# interstage_B1v2.net
KiCad netlist of a schematic drawn in EAGLE
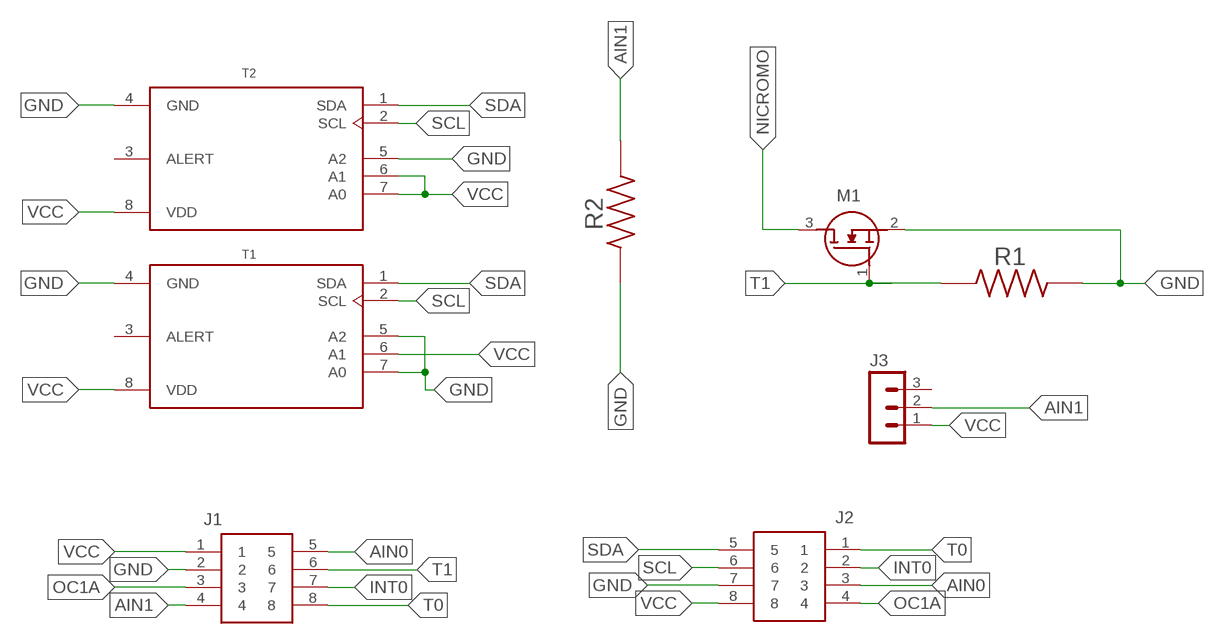
[diagram p0: schematic, sheet 1]

(export (version "E")
  (design (tool "Eeschema 10.0.6"))
  (components
    (comp (ref "J1")
      (value "53261-0871")
      (footprint "eagle-import:53261-0871")
      (fields (field (name "MOUSER_PART_NUMBER") "538-53261-0871"))
      (libsource (lib "eagle-import") (part "53261-0871"))
    )
    (comp (ref "J2")
      (value "53261-0871")
      (footprint "eagle-import:53261-0871")
      (fields (field (name "MOUSER_PART_NUMBER") "538-53261-0871"))
      (libsource (lib "eagle-import") (part "53261-0871"))
    )
    (comp (ref "J3")
      (value "MA03-1")
      (footprint "eagle-import:MA03-1")
      (libsource (lib "eagle-import") (part "MA03-1"))
    )
    (comp (ref "M1")
      (value "PMV16XNR")
      (footprint "eagle-import:SOT95P230X110-3N")
      (fields (field (name "MOUSER_PART_NUMBER") "771-PMV16XNR"))
      (libsource (lib "eagle-import") (part "PMV16XNR"))
    )
    (comp (ref "R1")
      (value "330")
      (footprint "eagle-import:RESC3216X70N")
      (fields
        (field (name "DIGI-KEY_PART_NUMBER") "P330BCCT-ND")
        (field (name "MF") "Panasonic Electronic")
        (field (name "MP") "ERA-8AEB331V")
      )
      (libsource (lib "eagle-import") (part "ERA-8AEB331V"))
    )
    (comp (ref "R2")
      (value "330")
      (footprint "eagle-import:RESC3216X70N")
      (fields
        (field (name "DIGI-KEY_PART_NUMBER") "P330BCCT-ND")
        (field (name "MF") "Panasonic Electronic")
        (field (name "MP") "ERA-8AEB331V")
      )
      (libsource (lib "eagle-import") (part "ERA-8AEB331V"))
    )
    (comp (ref "T1")
      (value "MCP9808T-E/MS")
      (footprint "eagle-import:SOP65P490X110-8N")
      (fields (field (name "DIGI-KEY_PART_NUMBER") "MCP9808T-E/MSCT-ND") (field (name "MF") "Microchip"))
      (libsource (lib "eagle-import") (part "MCP9808T-E/MS"))
    )
    (comp (ref "T2")
      (value "MCP9808T-E/MS")
      (footprint "eagle-import:SOP65P490X110-8N")
      (fields (field (name "DIGI-KEY_PART_NUMBER") "MCP9808T-E/MSCT-ND") (field (name "MF") "Microchip"))
      (libsource (lib "eagle-import") (part "MCP9808T-E/MS"))
    )
  )
  (nets
    (net (code "1") (name "AIN0") (class "Default")
      (node (ref "J1") (pin "5") (pinfunction "5_5") (pintype "bidirectional"))
      (node (ref "J2") (pin "3") (pinfunction "3_3") (pintype "bidirectional"))
    )
    (net (code "2") (name "AIN1") (class "Default")
      (node (ref "J1") (pin "4") (pinfunction "4_4") (pintype "bidirectional"))
      (node (ref "J3") (pin "2") (pinfunction "2_2") (pintype "passive"))
      (node (ref "R2") (pin "2") (pinfunction "2_2") (pintype "passive"))
    )
    (net (code "3") (name "GND") (class "Default")
      (node (ref "J1") (pin "2") (pinfunction "2_2") (pintype "bidirectional"))
      (node (ref "J2") (pin "7") (pinfunction "7_7") (pintype "bidirectional"))
      (node (ref "M1") (pin "2") (pinfunction "S_2") (pintype "bidirectional"))
      (node (ref "R1") (pin "2") (pinfunction "2_2") (pintype "passive"))
      (node (ref "R2") (pin "1") (pinfunction "1_1") (pintype "passive"))
      (node (ref "T1") (pin "4") (pinfunction "GND_4") (pintype "power_in"))
      (node (ref "T1") (pin "5") (pinfunction "A2_5") (pintype "input"))
      (node (ref "T1") (pin "7") (pinfunction "A0_7") (pintype "input"))
      (node (ref "T2") (pin "4") (pinfunction "GND_4") (pintype "power_in"))
      (node (ref "T2") (pin "5") (pinfunction "A2_5") (pintype "input"))
    )
    (net (code "4") (name "INT0") (class "Default")
      (node (ref "J1") (pin "7") (pinfunction "7_7") (pintype "bidirectional"))
      (node (ref "J2") (pin "2") (pinfunction "2_2") (pintype "bidirectional"))
    )
    (net (code "5") (name "NICROMO") (class "Default")
      (node (ref "M1") (pin "3") (pinfunction "D_3") (pintype "bidirectional"))
    )
    (net (code "6") (name "OC1A") (class "Default")
      (node (ref "J1") (pin "3") (pinfunction "3_3") (pintype "bidirectional"))
      (node (ref "J2") (pin "4") (pinfunction "4_4") (pintype "bidirectional"))
    )
    (net (code "7") (name "SCL") (class "Default")
      (node (ref "J2") (pin "6") (pinfunction "6_6") (pintype "bidirectional"))
      (node (ref "T1") (pin "2") (pinfunction "SCL_2") (pintype "input"))
      (node (ref "T2") (pin "2") (pinfunction "SCL_2") (pintype "input"))
    )
    (net (code "8") (name "SDA") (class "Default")
      (node (ref "J2") (pin "5") (pinfunction "5_5") (pintype "bidirectional"))
      (node (ref "T1") (pin "1") (pinfunction "SDA_1") (pintype "bidirectional"))
      (node (ref "T2") (pin "1") (pinfunction "SDA_1") (pintype "bidirectional"))
    )
    (net (code "9") (name "T0") (class "Default")
      (node (ref "J1") (pin "8") (pinfunction "8_8") (pintype "bidirectional"))
      (node (ref "J2") (pin "1") (pinfunction "1_1") (pintype "bidirectional"))
    )
    (net (code "10") (name "T1") (class "Default")
      (node (ref "J1") (pin "6") (pinfunction "6_6") (pintype "bidirectional"))
      (node (ref "M1") (pin "1") (pinfunction "G_1") (pintype "bidirectional"))
      (node (ref "R1") (pin "1") (pinfunction "1_1") (pintype "passive"))
    )
    (net (code "11") (name "VCC") (class "Default")
      (node (ref "J1") (pin "1") (pinfunction "1_1") (pintype "bidirectional"))
      (node (ref "J2") (pin "8") (pinfunction "8_8") (pintype "bidirectional"))
      (node (ref "J3") (pin "1") (pinfunction "1_1") (pintype "passive"))
      (node (ref "T1") (pin "6") (pinfunction "A1_6") (pintype "input"))
      (node (ref "T1") (pin "8") (pinfunction "VDD_8") (pintype "power_in"))
      (node (ref "T2") (pin "6") (pinfunction "A1_6") (pintype "input"))
      (node (ref "T2") (pin "7") (pinfunction "A0_7") (pintype "input"))
      (node (ref "T2") (pin "8") (pinfunction "VDD_8") (pintype "power_in"))
    )
    (net (code "12") (name "unconnected-(J3-Pad3)") (class "Default")
      (node (ref "J3") (pin "3") (pinfunction "3_3") (pintype "passive"))
    )
    (net (code "13") (name "unconnected-(T1-ALERT-Pad3)") (class "Default")
      (node (ref "T1") (pin "3") (pinfunction "ALERT_3") (pintype "output"))
    )
    (net (code "14") (name "unconnected-(T2-ALERT-Pad3)") (class "Default")
      (node (ref "T2") (pin "3") (pinfunction "ALERT_3") (pintype "output"))
    )
  )
)
